# 7_ADC_Acquisition.net
KiCad netlist of a schematic drawn in Altium Designer
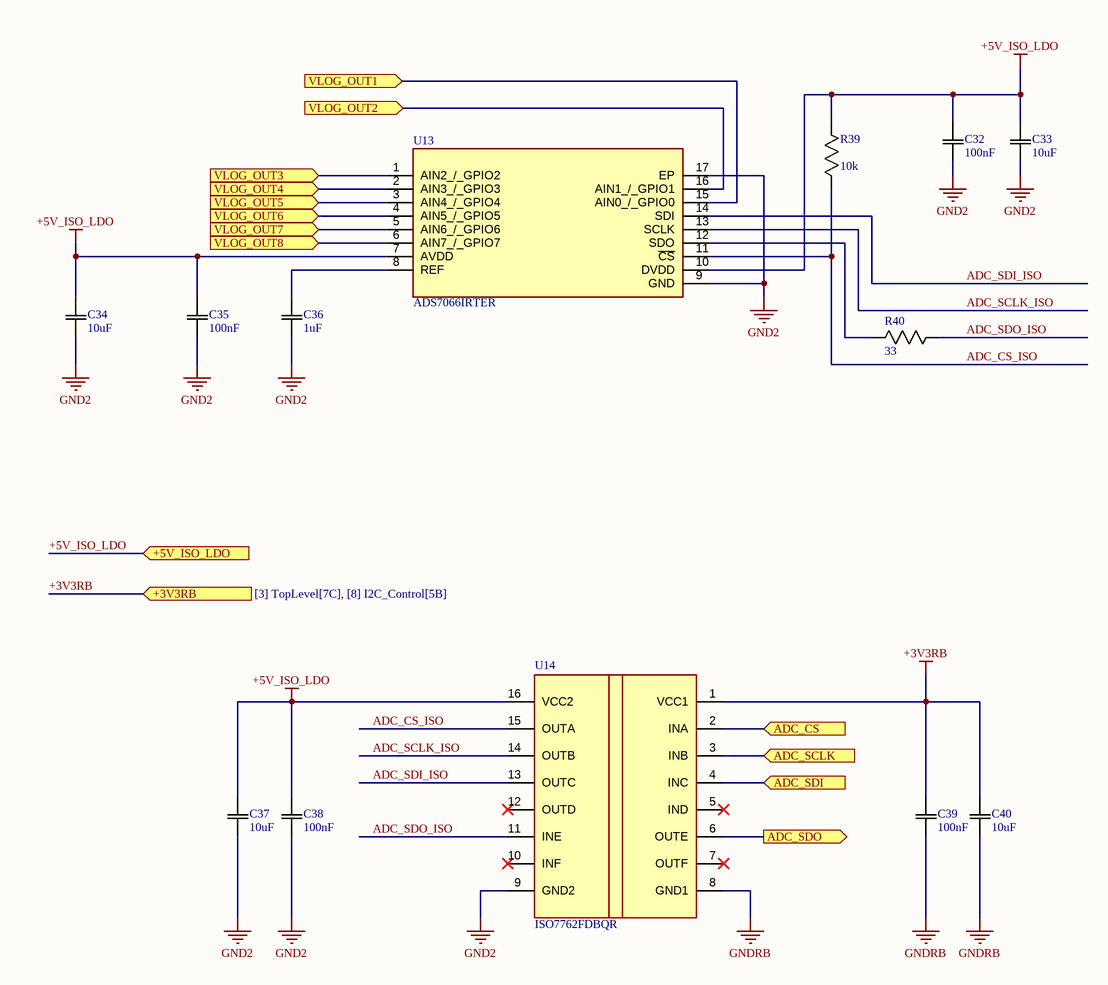
[diagram p0: [7] ADC_Acquisition.SchDoc]

(export (version "E")
  (design (tool "Eeschema 10.0.6"))
  (components
    (comp (ref "C32")
      (value "100nF")
      (footprint "CAPC1005X40N")
      (description "0.1 µF ±10% 50V Ceramic Capacitor X7R 0402 (1005 Metric)")
      (fields
        (field (name "MANUFACTURER_PART_NUMBER") "GCM155R71H104KE02D")
        (field (name "COPYRIGHT") "Copyright (C) 2026 Ultra Librarian. All rights reserved.")
      )
      (libsource (lib "PCEIOT") (part "GCM155R71H104KE02D"))
    )
    (comp (ref "C33")
      (value "10uF")
      (footprint "CAPC1005X40N")
      (description "10 µF ±20% 10V Ceramic Capacitor X5R 0402 (1005 Metric)")
      (fields
        (field (name "MANUFACTURER_PART_NUMBER") "GRT155R61A106ME13D")
        (field (name "COPYRIGHT") "Copyright (C) 2026 Ultra Librarian. All rights reserved.")
      )
      (libsource (lib "PCEIOT") (part "GRT155R61A106ME13D"))
    )
    (comp (ref "C34")
      (value "10uF")
      (footprint "CAPC1005X40N")
      (description "10 µF ±20% 10V Ceramic Capacitor X5R 0402 (1005 Metric)")
      (fields
        (field (name "MANUFACTURER_PART_NUMBER") "GRT155R61A106ME13D")
        (field (name "COPYRIGHT") "Copyright (C) 2026 Ultra Librarian. All rights reserved.")
      )
      (libsource (lib "PCEIOT") (part "GRT155R61A106ME13D"))
    )
    (comp (ref "C35")
      (value "100nF")
      (footprint "CAPC1005X40N")
      (description "0.1 µF ±10% 50V Ceramic Capacitor X7R 0402 (1005 Metric)")
      (fields
        (field (name "MANUFACTURER_PART_NUMBER") "GCM155R71H104KE02D")
        (field (name "COPYRIGHT") "Copyright (C) 2026 Ultra Librarian. All rights reserved.")
      )
      (libsource (lib "PCEIOT") (part "GCM155R71H104KE02D"))
    )
    (comp (ref "C36")
      (value "1uF")
      (footprint "CAPC1005X40N")
      (description "1 µF ±10% 10V Ceramic Capacitor X7R 0402 (1005 Metric)")
      (fields
        (field (name "MANUFACTURER_PART_NUMBER") "GRM155Z71A105KE01D")
        (field (name "COPYRIGHT") "Copyright (C) 2025 Ultra Librarian. All rights reserved.")
      )
      (libsource (lib "PCEIOT") (part "GRM155Z71A105KE01D"))
    )
    (comp (ref "C37")
      (value "10uF")
      (footprint "CAPC1005X40N")
      (description "10 µF ±20% 10V Ceramic Capacitor X5R 0402 (1005 Metric)")
      (fields
        (field (name "MANUFACTURER_PART_NUMBER") "GRT155R61A106ME13D")
        (field (name "COPYRIGHT") "Copyright (C) 2026 Ultra Librarian. All rights reserved.")
      )
      (libsource (lib "PCEIOT") (part "GRT155R61A106ME13D"))
    )
    (comp (ref "C38")
      (value "100nF")
      (footprint "CAPC1005X40N")
      (description "0.1 µF ±10% 50V Ceramic Capacitor X7R 0402 (1005 Metric)")
      (fields
        (field (name "MANUFACTURER_PART_NUMBER") "GCM155R71H104KE02D")
        (field (name "COPYRIGHT") "Copyright (C) 2026 Ultra Librarian. All rights reserved.")
      )
      (libsource (lib "PCEIOT") (part "GCM155R71H104KE02D"))
    )
    (comp (ref "C39")
      (value "100nF")
      (footprint "CAPC1005X40N")
      (description "0.1 µF ±10% 50V Ceramic Capacitor X7R 0402 (1005 Metric)")
      (fields
        (field (name "MANUFACTURER_PART_NUMBER") "GCM155R71H104KE02D")
        (field (name "COPYRIGHT") "Copyright (C) 2026 Ultra Librarian. All rights reserved.")
      )
      (libsource (lib "PCEIOT") (part "GCM155R71H104KE02D"))
    )
    (comp (ref "C40")
      (value "10uF")
      (footprint "CAPC1005X40N")
      (description "10 µF ±20% 10V Ceramic Capacitor X5R 0402 (1005 Metric)")
      (fields
        (field (name "MANUFACTURER_PART_NUMBER") "GRT155R61A106ME13D")
        (field (name "COPYRIGHT") "Copyright (C) 2026 Ultra Librarian. All rights reserved.")
      )
      (libsource (lib "PCEIOT") (part "GRT155R61A106ME13D"))
    )
    (comp (ref "R39")
      (value "10k")
      (footprint "RESC1005X40N")
      (description "10 kOhms ±1% 0.063W, 1/16W Chip Resistor 0402 (1005 Metric) Moisture Resistant Thick Film")
      (fields
        (field (name "MANUFACTURER_PART_NUMBER") "RC0402FR-0710KL")
        (field (name "COPYRIGHT") "Copyright (C) 2025 Ultra Librarian. All rights reserved.")
      )
      (libsource (lib "PCEIOT") (part "RC0402FR-0710KL"))
    )
    (comp (ref "R40")
      (value "33")
      (footprint "RESC1005X40N")
      (description "33 Ohms ±1% 0.063W, 1/16W Chip Resistor 0402 (1005 Metric) Moisture Resistant Thick Film")
      (fields
        (field (name "MANUFACTURER_PART_NUMBER") "RC0402FR-0733RL")
        (field (name "COPYRIGHT") "Copyright (C) 2025 Ultra Librarian. All rights reserved.")
      )
      (libsource (lib "PCEIOT") (part "RC0402FR-0733RL"))
    )
    (comp (ref "U13")
      (value "ADS7066IRTER")
      (footprint "QFN50P300X300X80-17N-D")
      (fields (field (name "MOUSER PART NUMBER") "595-ADS7066IRTER"))
      (libsource (lib "PCEIOT") (part "ADS7066IRTER"))
    )
    (comp (ref "U14")
      (value "ISO7762FDBQR")
      (footprint "SOP64P600X175-16N")
      (fields (field (name "COPYRIGHT") "Copyright (C) 2025 Ultra Librarian. All rights reserved."))
      (libsource (lib "PCEIOT") (part "ISO7762FDBQR"))
    )
  )
  (nets
    (net (code "1") (name "+3V3RB") (class "Default")
      (node (ref "C39") (pin "2") (pinfunction "2_2") (pintype "passive"))
      (node (ref "C40") (pin "2") (pinfunction "2_2") (pintype "passive"))
      (node (ref "U14") (pin "1") (pinfunction "VCC1_1") (pintype "passive"))
    )
    (net (code "2") (name "+5V_ISO_LDO") (class "Default")
      (node (ref "C32") (pin "2") (pinfunction "2_2") (pintype "passive"))
      (node (ref "C33") (pin "2") (pinfunction "2_2") (pintype "passive"))
      (node (ref "C34") (pin "2") (pinfunction "2_2") (pintype "passive"))
      (node (ref "C35") (pin "2") (pinfunction "2_2") (pintype "passive"))
      (node (ref "C37") (pin "2") (pinfunction "2_2") (pintype "passive"))
      (node (ref "C38") (pin "2") (pinfunction "2_2") (pintype "passive"))
      (node (ref "R39") (pin "1") (pinfunction "1_1") (pintype "passive"))
      (node (ref "U13") (pin "10") (pinfunction "DVDD_10") (pintype "passive"))
      (node (ref "U13") (pin "7") (pinfunction "AVDD_7") (pintype "passive"))
      (node (ref "U14") (pin "16") (pinfunction "VCC2_16") (pintype "passive"))
    )
    (net (code "3") (name "/ADC_CS") (class "Default")
      (node (ref "U14") (pin "2") (pinfunction "INA_2") (pintype "passive"))
    )
    (net (code "4") (name "/ADC_CS_ISO") (class "Default")
      (node (ref "R39") (pin "2") (pinfunction "2_2") (pintype "passive"))
      (node (ref "U13") (pin "11") (pinfunction "~{CS}_11") (pintype "passive"))
      (node (ref "U14") (pin "15") (pinfunction "OUTA_15") (pintype "passive"))
    )
    (net (code "5") (name "/ADC_SCLK") (class "Default")
      (node (ref "U14") (pin "3") (pinfunction "INB_3") (pintype "passive"))
    )
    (net (code "6") (name "/ADC_SCLK_ISO") (class "Default")
      (node (ref "U13") (pin "13") (pinfunction "SCLK_13") (pintype "passive"))
      (node (ref "U14") (pin "14") (pinfunction "OUTB_14") (pintype "passive"))
    )
    (net (code "7") (name "/ADC_SDI") (class "Default")
      (node (ref "U14") (pin "4") (pinfunction "INC_4") (pintype "passive"))
    )
    (net (code "8") (name "/ADC_SDI_ISO") (class "Default")
      (node (ref "U13") (pin "14") (pinfunction "SDI_14") (pintype "passive"))
      (node (ref "U14") (pin "13") (pinfunction "OUTC_13") (pintype "passive"))
    )
    (net (code "9") (name "/ADC_SDO") (class "Default")
      (node (ref "U14") (pin "6") (pinfunction "OUTE_6") (pintype "passive"))
    )
    (net (code "10") (name "/ADC_SDO_ISO") (class "Default")
      (node (ref "R40") (pin "1") (pinfunction "1_1") (pintype "passive"))
      (node (ref "U14") (pin "11") (pinfunction "INE_11") (pintype "passive"))
    )
    (net (code "11") (name "/VLOG_OUT1") (class "Default")
      (node (ref "U13") (pin "15") (pinfunction "AIN0_/_GPIO0_15") (pintype "passive"))
    )
    (net (code "12") (name "/VLOG_OUT2") (class "Default")
      (node (ref "U13") (pin "16") (pinfunction "AIN1_/_GPIO1_16") (pintype "passive"))
    )
    (net (code "13") (name "/VLOG_OUT3") (class "Default")
      (node (ref "U13") (pin "1") (pinfunction "AIN2_/_GPIO2_1") (pintype "passive"))
    )
    (net (code "14") (name "/VLOG_OUT4") (class "Default")
      (node (ref "U13") (pin "2") (pinfunction "AIN3_/_GPIO3_2") (pintype "passive"))
    )
    (net (code "15") (name "/VLOG_OUT5") (class "Default")
      (node (ref "U13") (pin "3") (pinfunction "AIN4_/_GPIO4_3") (pintype "passive"))
    )
    (net (code "16") (name "/VLOG_OUT6") (class "Default")
      (node (ref "U13") (pin "4") (pinfunction "AIN5_/_GPIO5_4") (pintype "passive"))
    )
    (net (code "17") (name "/VLOG_OUT7") (class "Default")
      (node (ref "U13") (pin "5") (pinfunction "AIN6_/_GPIO6_5") (pintype "passive"))
    )
    (net (code "18") (name "/VLOG_OUT8") (class "Default")
      (node (ref "U13") (pin "6") (pinfunction "AIN7_/_GPIO7_6") (pintype "passive"))
    )
    (net (code "19") (name "GND2") (class "Default")
      (node (ref "C32") (pin "1") (pinfunction "1_1") (pintype "passive"))
      (node (ref "C33") (pin "1") (pinfunction "1_1") (pintype "passive"))
      (node (ref "C34") (pin "1") (pinfunction "1_1") (pintype "passive"))
      (node (ref "C35") (pin "1") (pinfunction "1_1") (pintype "passive"))
      (node (ref "C36") (pin "1") (pinfunction "1_1") (pintype "passive"))
      (node (ref "C37") (pin "1") (pinfunction "1_1") (pintype "passive"))
      (node (ref "C38") (pin "1") (pinfunction "1_1") (pintype "passive"))
      (node (ref "U13") (pin "17") (pinfunction "EP_17") (pintype "passive"))
      (node (ref "U13") (pin "9") (pinfunction "GND_9") (pintype "passive"))
      (node (ref "U14") (pin "9") (pinfunction "GND2_9") (pintype "passive"))
    )
    (net (code "20") (name "GNDRB") (class "Default")
      (node (ref "C39") (pin "1") (pinfunction "1_1") (pintype "passive"))
      (node (ref "C40") (pin "1") (pinfunction "1_1") (pintype "passive"))
      (node (ref "U14") (pin "8") (pinfunction "GND1_8") (pintype "passive"))
    )
    (net (code "21") (name "Net-(U13-REF)") (class "Default")
      (node (ref "C36") (pin "2") (pinfunction "2_2") (pintype "passive"))
      (node (ref "U13") (pin "8") (pinfunction "REF_8") (pintype "passive"))
    )
    (net (code "22") (name "Net-(U13-SDO)") (class "Default")
      (node (ref "R40") (pin "2") (pinfunction "2_2") (pintype "passive"))
      (node (ref "U13") (pin "12") (pinfunction "SDO_12") (pintype "passive"))
    )
    (net (code "23") (name "unconnected-(U14-IND-Pad5)") (class "Default")
      (node (ref "U14") (pin "5") (pinfunction "IND_5") (pintype "passive+no_connect"))
    )
    (net (code "24") (name "unconnected-(U14-INF-Pad10)") (class "Default")
      (node (ref "U14") (pin "10") (pinfunction "INF_10") (pintype "passive+no_connect"))
    )
    (net (code "25") (name "unconnected-(U14-OUTD-Pad12)") (class "Default")
      (node (ref "U14") (pin "12") (pinfunction "OUTD_12") (pintype "passive+no_connect"))
    )
    (net (code "26") (name "unconnected-(U14-OUTF-Pad7)") (class "Default")
      (node (ref "U14") (pin "7") (pinfunction "OUTF_7") (pintype "passive+no_connect"))
    )
  )
)
